# ProProject_Paragliding-Sensor_2023-10-07.net
KiCad netlist of a schematic drawn in EasyEDA Pro
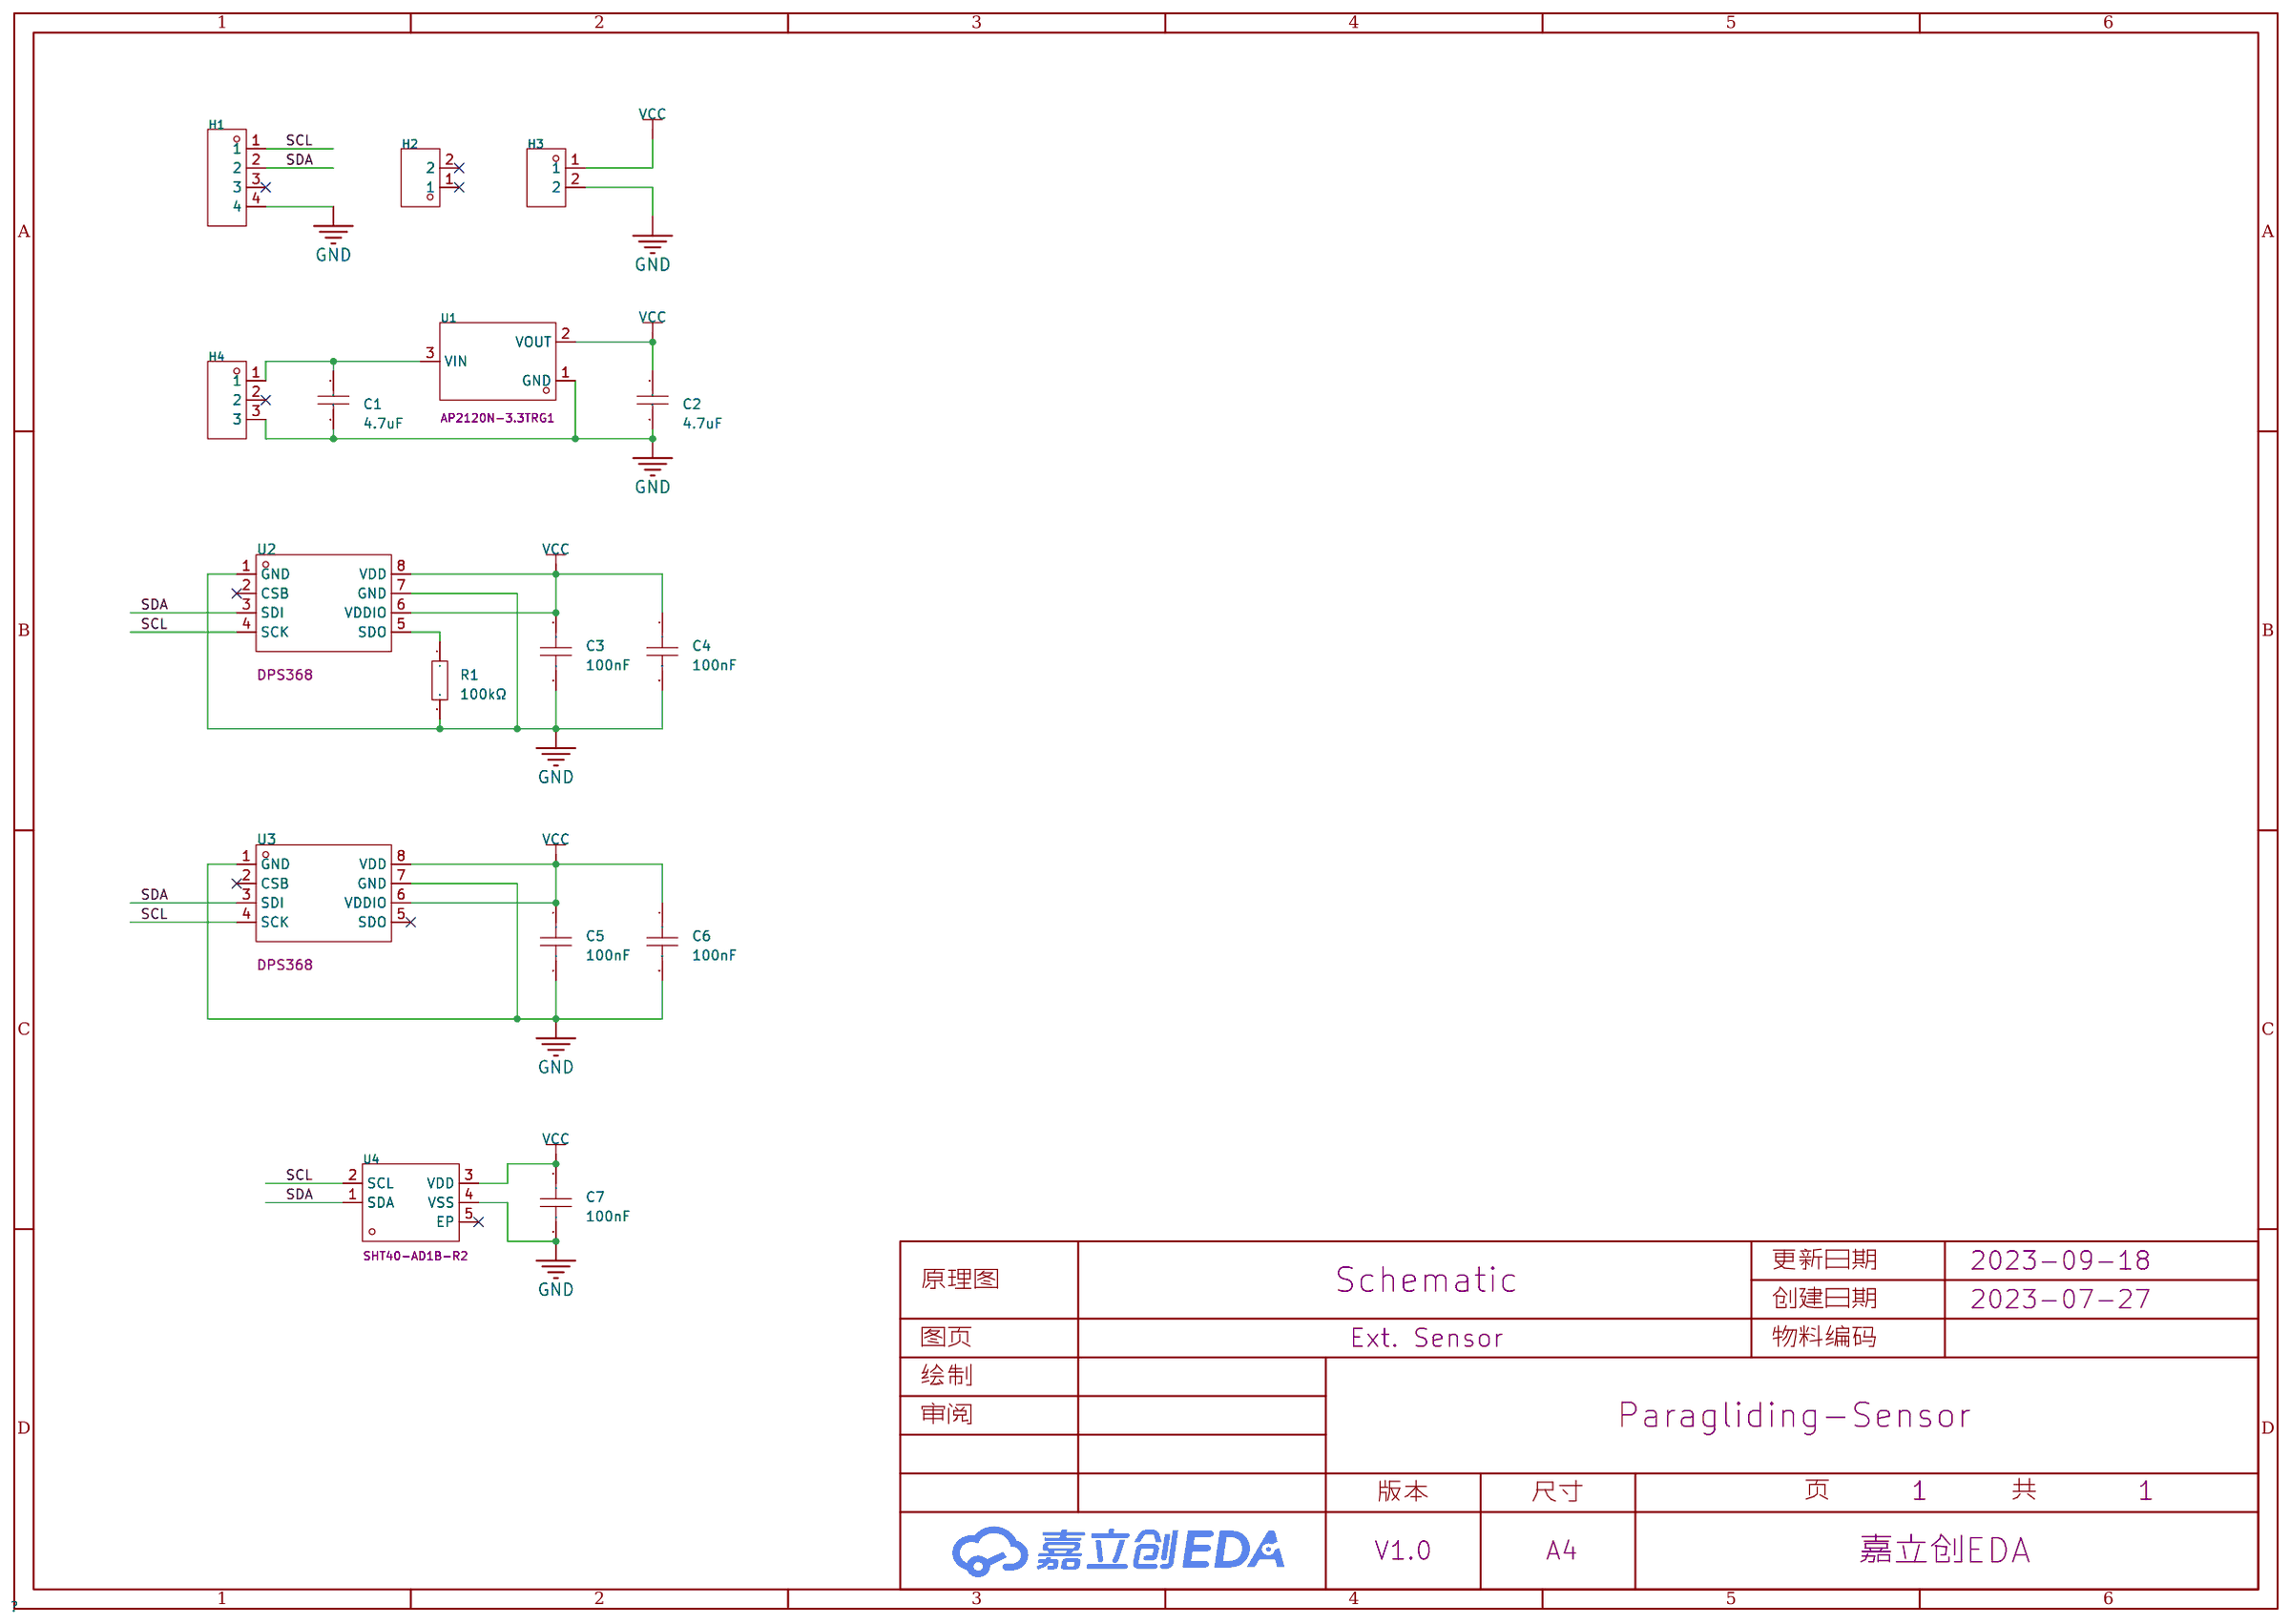
[diagram p0: schematic sheet]

(export (version "E")
  (design (tool "Eeschema 10.0.6"))
  (components
    (comp (ref "C1")
      (value "4.7uF")
      (footprint "easyedapro:C0402")
      (description "容值:4.7uF;精度:±20%;额定电压:10V;材质(温度系数):X5R;")
      (fields
        (field (name "Manufacturer Part") "CL05A475MP5NRNC")
        (field (name "Manufacturer") "SAMSUNG(三星)")
      )
      (libsource (lib "easyedapro") (part "CL05A475MP5NRNC"))
    )
    (comp (ref "C2")
      (value "4.7uF")
      (footprint "easyedapro:C0402")
      (description "容值:4.7uF;精度:±20%;额定电压:10V;材质(温度系数):X5R;")
      (fields
        (field (name "Manufacturer Part") "CL05A475MP5NRNC")
        (field (name "Manufacturer") "SAMSUNG(三星)")
      )
      (libsource (lib "easyedapro") (part "CL05A475MP5NRNC"))
    )
    (comp (ref "C3")
      (value "100nF")
      (footprint "easyedapro:C0201")
      (description "容值:100nF;精度:±10%;额定电压:10V;材质(温度系数):X7R;")
      (fields
        (field (name "Manufacturer Part") "GRM033Z71A104KE14D")
        (field (name "Manufacturer") "muRata(村田)")
      )
      (libsource (lib "easyedapro") (part "GRM033Z71A104KE14D"))
    )
    (comp (ref "C4")
      (value "100nF")
      (footprint "easyedapro:C0201")
      (description "容值:100nF;精度:±10%;额定电压:10V;材质(温度系数):X7R;")
      (fields
        (field (name "Manufacturer Part") "GRM033Z71A104KE14D")
        (field (name "Manufacturer") "muRata(村田)")
      )
      (libsource (lib "easyedapro") (part "GRM033Z71A104KE14D"))
    )
    (comp (ref "C5")
      (value "100nF")
      (footprint "easyedapro:C0201")
      (description "容值:100nF;精度:±10%;额定电压:10V;材质(温度系数):X7R;")
      (fields
        (field (name "Manufacturer Part") "GRM033Z71A104KE14D")
        (field (name "Manufacturer") "muRata(村田)")
      )
      (libsource (lib "easyedapro") (part "GRM033Z71A104KE14D"))
    )
    (comp (ref "C6")
      (value "100nF")
      (footprint "easyedapro:C0201")
      (description "容值:100nF;精度:±10%;额定电压:10V;材质(温度系数):X7R;")
      (fields
        (field (name "Manufacturer Part") "GRM033Z71A104KE14D")
        (field (name "Manufacturer") "muRata(村田)")
      )
      (libsource (lib "easyedapro") (part "GRM033Z71A104KE14D"))
    )
    (comp (ref "C7")
      (value "100nF")
      (footprint "easyedapro:C0201")
      (description "容值:100nF;精度:±10%;额定电压:10V;材质(温度系数):X7R;")
      (fields
        (field (name "Manufacturer Part") "GRM033Z71A104KE14D")
        (field (name "Manufacturer") "muRata(村田)")
      )
      (libsource (lib "easyedapro") (part "GRM033Z71A104KE14D"))
    )
    (comp (ref "H1")
      (value "PZ254V-11-04P")
      (footprint "easyedapro:HDR-TH_4P-P2.54-V-M")
      (fields (field (name "Manufacturer") "XFCN(兴飞)"))
      (libsource (lib "easyedapro") (part "PZ254V-11-04P_C2691448"))
    )
    (comp (ref "H2")
      (value "PZ254V-11-02P")
      (footprint "easyedapro:HDR-TH_2P-P2.54-V-M")
      (fields (field (name "Manufacturer") "XFCN(兴飞)"))
      (libsource (lib "easyedapro") (part "PZ254V-11-02P"))
    )
    (comp (ref "H3")
      (value "PZ254V-11-02P")
      (footprint "easyedapro:HDR-TH_2P-P2.54-V-M")
      (fields (field (name "Manufacturer") "XFCN(兴飞)"))
      (libsource (lib "easyedapro") (part "PZ254V-11-02P"))
    )
    (comp (ref "H4")
      (value "PZ254V-11-03P")
      (footprint "easyedapro:HDR-TH_3P-P2.54-V-M")
      (fields (field (name "Manufacturer") "XFCN(兴飞)"))
      (libsource (lib "easyedapro") (part "PZ254V-11-03P_C2937625"))
    )
    (comp (ref "R1")
      (value "100kΩ")
      (footprint "easyedapro:R0201")
      (description "电阻类型:厚膜电阻;阻值:100kΩ;精度:±1%;功率:50mW;")
      (fields
        (field (name "Manufacturer Part") "0201WMF1003TEE")
        (field (name "Manufacturer") "UNI-ROYAL(厚声)")
      )
      (libsource (lib "easyedapro") (part "0201WMF1003TEE"))
    )
    (comp (ref "U1")
      (value "AP2120N-3.3TRG1")
      (footprint "easyedapro:SOT-23-3_L2.9-W1.3-P1.90-LS2.4-BR")
      (description "输出类型:固定;输出极性:正;最大输入电压:6V;输出电压:3.3V;输出电流:150mA;电源纹波抑制比(PSRR):65dB@(1kHz);")
      (fields (field (name "Manufacturer Part") "AP2120N-3.3TRG1") (field (name "Manufacturer") "DIODES(美台)"))
      (libsource (lib "easyedapro") (part "AP2120N-3.3TRG1"))
    )
    (comp (ref "U2")
      (value "DPS368")
      (footprint "easyedapro:WLGA-8_L2.5-W2.0-P0.65-TR_DPS422")
      (fields (field (name "Manufacturer Part") "DPS368") (field (name "Manufacturer") "Infineon(英飞凌)"))
      (libsource (lib "easyedapro") (part "DPS368"))
    )
    (comp (ref "U3")
      (value "DPS368")
      (footprint "easyedapro:WLGA-8_L2.5-W2.0-P0.65-TR_DPS422")
      (fields (field (name "Manufacturer Part") "DPS368") (field (name "Manufacturer") "Infineon(英飞凌)"))
      (libsource (lib "easyedapro") (part "DPS368"))
    )
    (comp (ref "U4")
      (value "SHT40-AD1B-R2")
      (footprint "easyedapro:DFN-4_L1.5-W1.5-P0.8-TL-EP")
      (description "Latest relative humidity and temperature sensor generation: SHT4x, 2.5k TR size, RH/ T Sensor")
      (fields
        (field (name "Manufacturer Part") "SHT40-AD1B-R2")
        (field (name "Manufacturer") "Sensirion(瑞士盛思锐)")
      )
      (libsource (lib "easyedapro") (part "SHT40-AD1B-R2"))
    )
  )
  (nets
    (net (code "1") (name "/SCL") (class "Default")
      (node (ref "H1") (pin "1") (pinfunction "1_1") (pintype "input"))
      (node (ref "U2") (pin "4") (pinfunction "SCK_4") (pintype "input"))
      (node (ref "U3") (pin "4") (pinfunction "SCK_4") (pintype "input"))
      (node (ref "U4") (pin "2") (pinfunction "SCL_2") (pintype "input"))
    )
    (net (code "2") (name "/SDA") (class "Default")
      (node (ref "H1") (pin "2") (pinfunction "2_2") (pintype "input"))
      (node (ref "U2") (pin "3") (pinfunction "SDI_3") (pintype "input"))
      (node (ref "U3") (pin "3") (pinfunction "SDI_3") (pintype "input"))
      (node (ref "U4") (pin "1") (pinfunction "SDA_1") (pintype "input"))
    )
    (net (code "3") (name "GND") (class "Default")
      (node (ref "C1") (pin "2") (pinfunction "2_2") (pintype "input"))
      (node (ref "C2") (pin "2") (pinfunction "2_2") (pintype "input"))
      (node (ref "C3") (pin "2") (pinfunction "2_2") (pintype "input"))
      (node (ref "C4") (pin "2") (pinfunction "2_2") (pintype "input"))
      (node (ref "C5") (pin "2") (pinfunction "2_2") (pintype "input"))
      (node (ref "C6") (pin "2") (pinfunction "2_2") (pintype "input"))
      (node (ref "C7") (pin "2") (pinfunction "2_2") (pintype "input"))
      (node (ref "H1") (pin "4") (pinfunction "4_4") (pintype "input"))
      (node (ref "H3") (pin "2") (pinfunction "2_2") (pintype "input"))
      (node (ref "H4") (pin "3") (pinfunction "3_3") (pintype "input"))
      (node (ref "R1") (pin "2") (pinfunction "2_2") (pintype "input"))
      (node (ref "U1") (pin "1") (pinfunction "GND_1") (pintype "input"))
      (node (ref "U2") (pin "1") (pinfunction "GND_1") (pintype "input"))
      (node (ref "U2") (pin "7") (pinfunction "GND_7") (pintype "input"))
      (node (ref "U3") (pin "1") (pinfunction "GND_1") (pintype "input"))
      (node (ref "U3") (pin "7") (pinfunction "GND_7") (pintype "input"))
      (node (ref "U4") (pin "4") (pinfunction "VSS_4") (pintype "input"))
    )
    (net (code "4") (name "Net-(U1-VIN)") (class "Default")
      (node (ref "C1") (pin "1") (pinfunction "1_1") (pintype "input"))
      (node (ref "H4") (pin "1") (pinfunction "1_1") (pintype "input"))
      (node (ref "U1") (pin "3") (pinfunction "VIN_3") (pintype "input"))
    )
    (net (code "5") (name "Net-(U2-SDO)") (class "Default")
      (node (ref "R1") (pin "1") (pinfunction "1_1") (pintype "input"))
      (node (ref "U2") (pin "5") (pinfunction "SDO_5") (pintype "input"))
    )
    (net (code "6") (name "VCC") (class "Default")
      (node (ref "C2") (pin "1") (pinfunction "1_1") (pintype "input"))
      (node (ref "C3") (pin "1") (pinfunction "1_1") (pintype "input"))
      (node (ref "C4") (pin "1") (pinfunction "1_1") (pintype "input"))
      (node (ref "C5") (pin "1") (pinfunction "1_1") (pintype "input"))
      (node (ref "C6") (pin "1") (pinfunction "1_1") (pintype "input"))
      (node (ref "C7") (pin "1") (pinfunction "1_1") (pintype "input"))
      (node (ref "H3") (pin "1") (pinfunction "1_1") (pintype "input"))
      (node (ref "U1") (pin "2") (pinfunction "VOUT_2") (pintype "input"))
      (node (ref "U2") (pin "6") (pinfunction "VDDIO_6") (pintype "input"))
      (node (ref "U2") (pin "8") (pinfunction "VDD_8") (pintype "input"))
      (node (ref "U3") (pin "6") (pinfunction "VDDIO_6") (pintype "input"))
      (node (ref "U3") (pin "8") (pinfunction "VDD_8") (pintype "input"))
      (node (ref "U4") (pin "3") (pinfunction "VDD_3") (pintype "input"))
    )
    (net (code "7") (name "unconnected-(H1-Pad3)") (class "Default")
      (node (ref "H1") (pin "3") (pinfunction "3_3") (pintype "input+no_connect"))
    )
    (net (code "8") (name "unconnected-(H2-Pad1)") (class "Default")
      (node (ref "H2") (pin "1") (pinfunction "1_1") (pintype "input+no_connect"))
    )
    (net (code "9") (name "unconnected-(H2-Pad2)") (class "Default")
      (node (ref "H2") (pin "2") (pinfunction "2_2") (pintype "input+no_connect"))
    )
    (net (code "10") (name "unconnected-(H4-Pad2)") (class "Default")
      (node (ref "H4") (pin "2") (pinfunction "2_2") (pintype "input+no_connect"))
    )
    (net (code "11") (name "unconnected-(U2-CSB-Pad2)") (class "Default")
      (node (ref "U2") (pin "2") (pinfunction "CSB_2") (pintype "input+no_connect"))
    )
    (net (code "12") (name "unconnected-(U3-CSB-Pad2)") (class "Default")
      (node (ref "U3") (pin "2") (pinfunction "CSB_2") (pintype "input+no_connect"))
    )
    (net (code "13") (name "unconnected-(U3-SDO-Pad5)") (class "Default")
      (node (ref "U3") (pin "5") (pinfunction "SDO_5") (pintype "input+no_connect"))
    )
    (net (code "14") (name "unconnected-(U4-EP-Pad5)") (class "Default")
      (node (ref "U4") (pin "5") (pinfunction "EP_5") (pintype "input+no_connect"))
    )
  )
)
